# CAN_Controller.net
KiCad netlist of a schematic drawn in Altium Designer
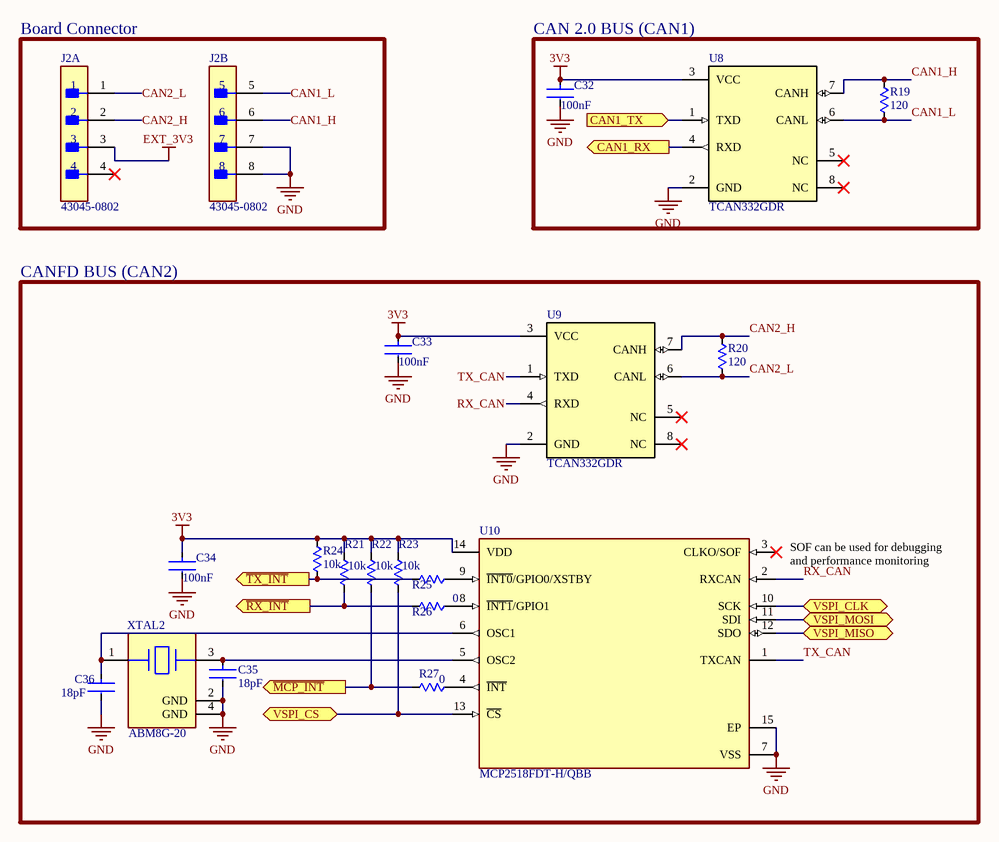
[diagram p0: CAN_Controller.SchDoc]

(export (version "E")
  (design (tool "Eeschema 10.0.6"))
  (components
    (comp (ref "C32")
      (value "100nF")
      (footprint "FP-CL10-IPC_B")
      (description "0.1 µF ±10% 50V Ceramic Capacitor X7R 0603 (1608 Metric)")
      (fields (field (name "Comment") "CL10B104KB8WPNC"))
      (libsource (lib "UCalgary Racing - Power Electronics") (part "CAPACITOR"))
    )
    (comp (ref "C33")
      (value "100nF")
      (footprint "FP-CL10-IPC_B")
      (description "0.1 µF ±10% 50V Ceramic Capacitor X7R 0603 (1608 Metric)")
      (fields (field (name "Comment") "CL10B104KB8WPNC"))
      (libsource (lib "UCalgary Racing - Power Electronics") (part "CAPACITOR"))
    )
    (comp (ref "C34")
      (value "100nF")
      (footprint "FP-CL10-IPC_B")
      (description "0.1 µF ±10% 50V Ceramic Capacitor X7R 0603 (1608 Metric)")
      (fields (field (name "Comment") "CL10B104KB8WPNC"))
      (libsource (lib "UCalgary Racing - Power Electronics") (part "CAPACITOR"))
    )
    (comp (ref "C35")
      (value "18pF")
      (footprint "FP-C0402-BB-MFG")
      (fields (field (name "Comment") "C0402C180J3GACAUTO"))
      (libsource (lib "UCalgary Racing - Power Electronics") (part "CAPACITOR"))
    )
    (comp (ref "C36")
      (value "18pF")
      (footprint "FP-C0402-BB-MFG")
      (fields (field (name "Comment") "C0402C180J3GACAUTO"))
      (libsource (lib "UCalgary Racing - Power Electronics") (part "CAPACITOR"))
    )
    (comp (ref "J2")
      (value "43045-0802")
      (footprint "FP-43045-0802-MFG")
      (description "CONN HEADER R/A 8POS 3MM")
      (libsource (lib "UCalgary Racing - Power Electronics") (part "85438c39ca9ef07d43bb2e97c52bc44"))
    )
    (comp (ref "R19")
      (value "120")
      (footprint "FP-CRCW0603-e3-IPC_B")
      (description "120 Ohms ±1% 0.1W, 1/10W Chip Resistor 0603 (1608 Metric) Automotive AEC-Q200 Thick Film")
      (fields (field (name "POWER") "100mW") (field (name "TOLERANCE") "1%"))
      (libsource (lib "UCalgary Racing - Power Electronics") (part "RESISTOR"))
    )
    (comp (ref "R20")
      (value "120")
      (footprint "FP-CRCW0603-e3-IPC_B")
      (description "120 Ohms ±1% 0.1W, 1/10W Chip Resistor 0603 (1608 Metric) Automotive AEC-Q200 Thick Film")
      (fields (field (name "POWER") "100mW") (field (name "TOLERANCE") "1%"))
      (libsource (lib "UCalgary Racing - Power Electronics") (part "RESISTOR"))
    )
    (comp (ref "R21")
      (value "10k")
      (footprint "FP-CRCW0603-e3-IPC_B")
      (description "10 kOhms ±1% 0.1W, 1/10W Chip Resistor 0603 (1608 Metric) Automotive AEC-Q200 Thick Film")
      (fields (field (name "POWER") "100mW") (field (name "TOLERANCE") "1%"))
      (libsource (lib "UCalgary Racing - Power Electronics") (part "RESISTOR"))
    )
    (comp (ref "R22")
      (value "10k")
      (footprint "FP-CRCW0603-e3-IPC_B")
      (description "10 kOhms ±1% 0.1W, 1/10W Chip Resistor 0603 (1608 Metric) Automotive AEC-Q200 Thick Film")
      (fields (field (name "POWER") "100mW") (field (name "TOLERANCE") "1%"))
      (libsource (lib "UCalgary Racing - Power Electronics") (part "RESISTOR"))
    )
    (comp (ref "R23")
      (value "10k")
      (footprint "FP-CRCW0603-e3-IPC_B")
      (description "10 kOhms ±1% 0.1W, 1/10W Chip Resistor 0603 (1608 Metric) Automotive AEC-Q200 Thick Film")
      (fields (field (name "POWER") "100mW") (field (name "TOLERANCE") "1%"))
      (libsource (lib "UCalgary Racing - Power Electronics") (part "RESISTOR"))
    )
    (comp (ref "R24")
      (value "10k")
      (footprint "FP-CRCW0603-e3-IPC_B")
      (description "10 kOhms ±1% 0.1W, 1/10W Chip Resistor 0603 (1608 Metric) Automotive AEC-Q200 Thick Film")
      (fields (field (name "POWER") "100mW") (field (name "TOLERANCE") "1%"))
      (libsource (lib "UCalgary Racing - Power Electronics") (part "RESISTOR"))
    )
    (comp (ref "R25")
      (value "CRCW06030000Z0EA")
      (footprint "FP-CRCW0603-e3-IPC_B")
      (description "0 Ohms Jumper Chip Resistor 0603 (1608 Metric) Automotive AEC-Q200 Thick Film")
      (libsource (lib "UCalgary Racing - Power Electronics") (part "RESISTOR"))
    )
    (comp (ref "R26")
      (value "0")
      (footprint "FP-CRCW0603-e3-IPC_B")
      (description "0 Ohms Jumper Chip Resistor 0603 (1608 Metric) Automotive AEC-Q200 Thick Film")
      (fields (field (name "Comment") "CRCW06030000Z0EA"))
      (libsource (lib "UCalgary Racing - Power Electronics") (part "RESISTOR"))
    )
    (comp (ref "R27")
      (value "0")
      (footprint "FP-CRCW0603-e3-IPC_B")
      (description "0 Ohms Jumper Chip Resistor 0603 (1608 Metric) Automotive AEC-Q200 Thick Film")
      (fields (field (name "Comment") "CRCW06030000Z0EA"))
      (libsource (lib "UCalgary Racing - Power Electronics") (part "RESISTOR"))
    )
    (comp (ref "U8")
      (value "TCAN332GDR")
      (footprint "TCAN332GDR-Footprint-1")
      (description "3.3-V CAN Transceiver with CAN FD")
      (libsource (lib "UCalgary Racing - Power Electronics") (part "TCAN332GDR-Symbol-1"))
    )
    (comp (ref "U9")
      (value "TCAN332GDR")
      (footprint "TCAN332GDR-Footprint-1")
      (description "3.3-V CAN Transceiver with CAN FD")
      (libsource (lib "UCalgary Racing - Power Electronics") (part "TCAN332GDR-Symbol-1"))
    )
    (comp (ref "U10")
      (value "MCP2518FDT-H/QBB")
      (footprint "FP-C04-21361-IPC_A")
      (description "1 Channel(s), 8MBps, CMOS, PDCC14")
      (libsource (lib "UCalgary Racing - Power Electronics") (part "171200ff88dd600c7d3e4b98ff00d41"))
    )
    (comp (ref "XTAL2")
      (value "ABM8G-20")
      (footprint "FP-ABM8G-MFG")
      (description "Crystal 20MHz ±20ppm (Tol) ±30ppm (Stability) 18pF FUND 80Ohm 4-Pin Ultra Mini-CSMD T/R")
      (libsource (lib "UCalgary Racing - Power Electronics") (part "48e526d86b7f2615d98721063c72f49"))
    )
  )
  (nets
    (net (code "1") (name "/CAN1_H") (class "Default")
      (node (ref "J2") (pin "6") (pinfunction "6_6") (pintype "passive"))
      (node (ref "R19") (pin "2") (pinfunction "2_2") (pintype "passive"))
      (node (ref "U8") (pin "7") (pinfunction "CANH_7") (pintype "bidirectional"))
    )
    (net (code "2") (name "/CAN1_L") (class "Default")
      (node (ref "J2") (pin "5") (pinfunction "5_5") (pintype "passive"))
      (node (ref "R19") (pin "1") (pinfunction "1_1") (pintype "passive"))
      (node (ref "U8") (pin "6") (pinfunction "CANL_6") (pintype "bidirectional"))
    )
    (net (code "3") (name "/CAN1_RX") (class "Default")
      (node (ref "U8") (pin "4") (pinfunction "RXD_4") (pintype "output"))
    )
    (net (code "4") (name "/CAN1_TX") (class "Default")
      (node (ref "U8") (pin "1") (pinfunction "TXD_1") (pintype "input"))
    )
    (net (code "5") (name "/CAN2_H") (class "Default")
      (node (ref "J2") (pin "2") (pinfunction "2_2") (pintype "passive"))
      (node (ref "R20") (pin "2") (pinfunction "2_2") (pintype "passive"))
      (node (ref "U9") (pin "7") (pinfunction "CANH_7") (pintype "bidirectional"))
    )
    (net (code "6") (name "/CAN2_L") (class "Default")
      (node (ref "J2") (pin "1") (pinfunction "1_1") (pintype "passive"))
      (node (ref "R20") (pin "1") (pinfunction "1_1") (pintype "passive"))
      (node (ref "U9") (pin "6") (pinfunction "CANL_6") (pintype "bidirectional"))
    )
    (net (code "7") (name "/MCP_INT") (class "Default")
      (node (ref "R22") (pin "1") (pinfunction "1_1") (pintype "passive"))
      (node (ref "R27") (pin "1") (pinfunction "1_1") (pintype "passive"))
    )
    (net (code "8") (name "/RX_CAN") (class "Default")
      (node (ref "U10") (pin "2") (pinfunction "RXCAN_2") (pintype "input"))
      (node (ref "U9") (pin "4") (pinfunction "RXD_4") (pintype "output"))
    )
    (net (code "9") (name "/RX_INT") (class "Default")
      (node (ref "R21") (pin "1") (pinfunction "1_1") (pintype "passive"))
      (node (ref "R26") (pin "1") (pinfunction "1_1") (pintype "passive"))
    )
    (net (code "10") (name "/TX_CAN") (class "Default")
      (node (ref "U10") (pin "1") (pinfunction "TXCAN_1") (pintype "passive"))
      (node (ref "U9") (pin "1") (pinfunction "TXD_1") (pintype "input"))
    )
    (net (code "11") (name "/TX_INT") (class "Default")
      (node (ref "R24") (pin "1") (pinfunction "1_1") (pintype "passive"))
      (node (ref "R25") (pin "1") (pinfunction "1_1") (pintype "passive"))
    )
    (net (code "12") (name "/VSPI_CLK") (class "Default")
      (node (ref "U10") (pin "10") (pinfunction "SCK_10") (pintype "input"))
    )
    (net (code "13") (name "/VSPI_CS") (class "Default")
      (node (ref "R23") (pin "1") (pinfunction "1_1") (pintype "passive"))
      (node (ref "U10") (pin "13") (pinfunction "~{CS}_13") (pintype "input"))
    )
    (net (code "14") (name "/VSPI_MISO") (class "Default")
      (node (ref "U10") (pin "12") (pinfunction "SDO_12") (pintype "bidirectional"))
    )
    (net (code "15") (name "/VSPI_MOSI") (class "Default")
      (node (ref "U10") (pin "11") (pinfunction "SDI_11") (pintype "input"))
    )
    (net (code "16") (name "3V3") (class "Default")
      (node (ref "C32") (pin "1") (pinfunction "1_1") (pintype "passive"))
      (node (ref "C33") (pin "1") (pinfunction "1_1") (pintype "passive"))
      (node (ref "C34") (pin "1") (pinfunction "1_1") (pintype "passive"))
      (node (ref "R21") (pin "2") (pinfunction "2_2") (pintype "passive"))
      (node (ref "R22") (pin "2") (pinfunction "2_2") (pintype "passive"))
      (node (ref "R23") (pin "2") (pinfunction "2_2") (pintype "passive"))
      (node (ref "R24") (pin "2") (pinfunction "2_2") (pintype "passive"))
      (node (ref "U10") (pin "14") (pinfunction "VDD_14") (pintype "power_in"))
      (node (ref "U8") (pin "3") (pinfunction "VCC_3") (pintype "power_in"))
      (node (ref "U9") (pin "3") (pinfunction "VCC_3") (pintype "power_in"))
    )
    (net (code "17") (name "EXT_3V3") (class "Default")
      (node (ref "J2") (pin "3") (pinfunction "3_3") (pintype "passive"))
    )
    (net (code "18") (name "GND") (class "Default")
      (node (ref "C32") (pin "2") (pinfunction "2_2") (pintype "passive"))
      (node (ref "C33") (pin "2") (pinfunction "2_2") (pintype "passive"))
      (node (ref "C34") (pin "2") (pinfunction "2_2") (pintype "passive"))
      (node (ref "C35") (pin "2") (pinfunction "2_2") (pintype "passive"))
      (node (ref "C36") (pin "2") (pinfunction "2_2") (pintype "passive"))
      (node (ref "J2") (pin "7") (pinfunction "7_7") (pintype "passive"))
      (node (ref "J2") (pin "8") (pinfunction "8_8") (pintype "passive"))
      (node (ref "U10") (pin "15") (pinfunction "EP_15") (pintype "power_in"))
      (node (ref "U10") (pin "7") (pinfunction "VSS_7") (pintype "power_in"))
      (node (ref "U8") (pin "2") (pinfunction "GND_2") (pintype "power_in"))
      (node (ref "U9") (pin "2") (pinfunction "GND_2") (pintype "power_in"))
      (node (ref "XTAL2") (pin "2") (pinfunction "GND_2") (pintype "power_in"))
      (node (ref "XTAL2") (pin "4") (pinfunction "GND_4") (pintype "power_in"))
    )
    (net (code "19") (name "Net-(U10-OSC1)") (class "Default")
      (node (ref "C36") (pin "1") (pinfunction "1_1") (pintype "passive"))
      (node (ref "U10") (pin "6") (pinfunction "OSC1_6") (pintype "output"))
      (node (ref "XTAL2") (pin "1") (pinfunction "1_1") (pintype "passive"))
    )
    (net (code "20") (name "Net-(U10-OSC2)") (class "Default")
      (node (ref "C35") (pin "1") (pinfunction "1_1") (pintype "passive"))
      (node (ref "U10") (pin "5") (pinfunction "OSC2_5") (pintype "output"))
      (node (ref "XTAL2") (pin "3") (pinfunction "3_3") (pintype "passive"))
    )
    (net (code "21") (name "Net-(U10-~{INT0}{slash}GPIO0{slash}XSTBY)") (class "Default")
      (node (ref "R25") (pin "2") (pinfunction "2_2") (pintype "passive"))
      (node (ref "U10") (pin "9") (pinfunction "~{INT0}/GPIO0/XSTBY_9") (pintype "input"))
    )
    (net (code "22") (name "Net-(U10-~{INT1}{slash}GPIO1)") (class "Default")
      (node (ref "R26") (pin "2") (pinfunction "2_2") (pintype "passive"))
      (node (ref "U10") (pin "8") (pinfunction "~{INT1}/GPIO1_8") (pintype "input"))
    )
    (net (code "23") (name "Net-(U10-~{INT})") (class "Default")
      (node (ref "R27") (pin "2") (pinfunction "2_2") (pintype "passive"))
      (node (ref "U10") (pin "4") (pinfunction "~{INT}_4") (pintype "output"))
    )
    (net (code "24") (name "unconnected-(J2-Pad4)") (class "Default")
      (node (ref "J2") (pin "4") (pinfunction "4_4") (pintype "passive+no_connect"))
    )
    (net (code "25") (name "unconnected-(U8-NC-Pad5)") (class "Default")
      (node (ref "U8") (pin "5") (pinfunction "NC_5") (pintype "passive+no_connect"))
    )
    (net (code "26") (name "unconnected-(U8-NC-Pad8)") (class "Default")
      (node (ref "U8") (pin "8") (pinfunction "NC_8") (pintype "passive+no_connect"))
    )
    (net (code "27") (name "unconnected-(U9-NC-Pad5)") (class "Default")
      (node (ref "U9") (pin "5") (pinfunction "NC_5") (pintype "passive+no_connect"))
    )
    (net (code "28") (name "unconnected-(U9-NC-Pad8)") (class "Default")
      (node (ref "U9") (pin "8") (pinfunction "NC_8") (pintype "passive+no_connect"))
    )
    (net (code "29") (name "unconnected-(U10-CLKO{slash}SOF-Pad3)") (class "Default")
      (node (ref "U10") (pin "3") (pinfunction "CLKO/SOF_3") (pintype "input+no_connect"))
    )
  )
)
